# comunicacion_serial.net
KiCad netlist of a schematic drawn in EAGLE
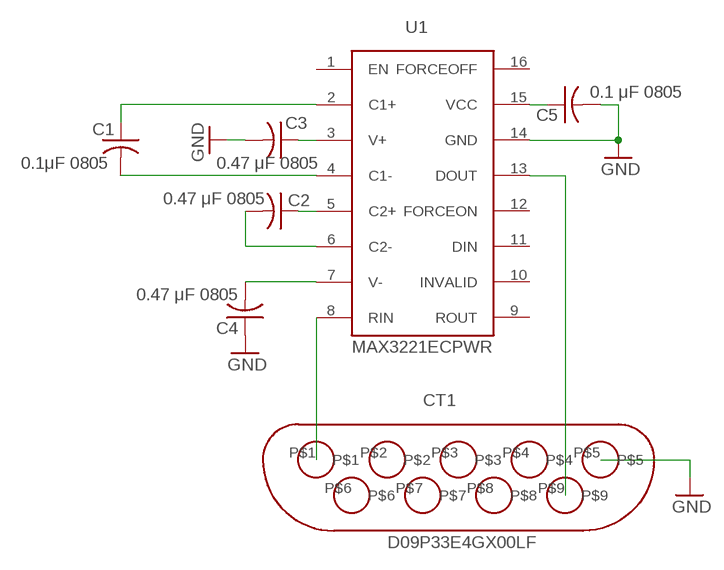
[diagram p0: schematic, sheet 1]

(export (version "E")
  (design (tool "Eeschema 10.0.6"))
  (components
    (comp (ref "C1")
      (value "0.1μF 0805")
      (footprint "eagle-import:C0805")
      (fields (field (name "PARTNO") "GCM21BR72A104KA37L"))
      (libsource (lib "eagle-import") (part "C-USC0805"))
    )
    (comp (ref "C2")
      (value "0.47 μF 0805")
      (footprint "eagle-import:C0805")
      (fields (field (name "PARTNO") "GCM21BR71H474KA55L"))
      (libsource (lib "eagle-import") (part "C-USC0805"))
    )
    (comp (ref "C3")
      (value "0.47 μF 0805")
      (footprint "eagle-import:C0805")
      (fields (field (name "PARTNO") "GCM21BR71H474KA55L"))
      (libsource (lib "eagle-import") (part "C-USC0805"))
    )
    (comp (ref "C4")
      (value "0.47 μF 0805")
      (footprint "eagle-import:C0805")
      (fields (field (name "PARTNO") "GCM21BR71H474KA55L"))
      (libsource (lib "eagle-import") (part "C-USC0805"))
    )
    (comp (ref "C5")
      (value "0.1 μF 0805")
      (footprint "eagle-import:C0805")
      (fields (field (name "PARTNO") "GCM21BR72A104KA37L"))
      (libsource (lib "eagle-import") (part "C-USC0805"))
    )
    (comp (ref "CT1")
      (value "D09P33E4GX00LF")
      (footprint "eagle-import:JEDEC")
      (libsource (lib "eagle-import") (part "D09P33E4GX00LF"))
    )
    (comp (ref "U1")
      (value "MAX3221ECPWR")
      (footprint "eagle-import:TSSOP")
      (libsource (lib "eagle-import") (part "MAX3221ECPWR"))
    )
  )
  (nets
    (net (code "1") (name "GND") (class "Default")
      (node (ref "C3") (pin "2") (pinfunction "2_2") (pintype "passive"))
      (node (ref "C4") (pin "1") (pinfunction "1_1") (pintype "passive"))
      (node (ref "C5") (pin "2") (pinfunction "2_2") (pintype "passive"))
      (node (ref "CT1") (pin "P$5") (pinfunction "P$5_P$5") (pintype "passive"))
      (node (ref "U1") (pin "14") (pinfunction "GND_14") (pintype "power_in"))
    )
    (net (code "2") (name "Net-(U1-C1+)") (class "Default")
      (node (ref "C1") (pin "1") (pinfunction "1_1") (pintype "passive"))
      (node (ref "U1") (pin "2") (pinfunction "C1+_2") (pintype "passive"))
    )
    (net (code "3") (name "Net-(U1-C1-)") (class "Default")
      (node (ref "C1") (pin "2") (pinfunction "2_2") (pintype "passive"))
      (node (ref "U1") (pin "4") (pinfunction "C1-_4") (pintype "passive"))
    )
    (net (code "4") (name "Net-(U1-C2+)") (class "Default")
      (node (ref "C2") (pin "1") (pinfunction "1_1") (pintype "passive"))
      (node (ref "U1") (pin "5") (pinfunction "C2+_5") (pintype "passive"))
    )
    (net (code "5") (name "Net-(U1-C2-)") (class "Default")
      (node (ref "C2") (pin "2") (pinfunction "2_2") (pintype "passive"))
      (node (ref "U1") (pin "6") (pinfunction "C2-_6") (pintype "passive"))
    )
    (net (code "6") (name "Net-(U1-DOUT)") (class "Default")
      (node (ref "CT1") (pin "P$9") (pinfunction "P$9_P$9") (pintype "passive"))
      (node (ref "U1") (pin "13") (pinfunction "DOUT_13") (pintype "output"))
    )
    (net (code "7") (name "Net-(U1-RIN)") (class "Default")
      (node (ref "CT1") (pin "P$1") (pinfunction "P$1_P$1") (pintype "passive"))
      (node (ref "U1") (pin "8") (pinfunction "RIN_8") (pintype "input"))
    )
    (net (code "8") (name "Net-(U1-V+)") (class "Default")
      (node (ref "C3") (pin "1") (pinfunction "1_1") (pintype "passive"))
      (node (ref "U1") (pin "3") (pinfunction "V+_3") (pintype "output"))
    )
    (net (code "9") (name "Net-(U1-V-)") (class "Default")
      (node (ref "C4") (pin "2") (pinfunction "2_2") (pintype "passive"))
      (node (ref "U1") (pin "7") (pinfunction "V-_7") (pintype "output"))
    )
    (net (code "10") (name "Net-(U1-VCC)") (class "Default")
      (node (ref "C5") (pin "1") (pinfunction "1_1") (pintype "passive"))
      (node (ref "U1") (pin "15") (pinfunction "VCC_15") (pintype "power_in"))
    )
    (net (code "11") (name "unconnected-(CT1-PadP$2)") (class "Default")
      (node (ref "CT1") (pin "P$2") (pinfunction "P$2_P$2") (pintype "passive"))
    )
    (net (code "12") (name "unconnected-(CT1-PadP$3)") (class "Default")
      (node (ref "CT1") (pin "P$3") (pinfunction "P$3_P$3") (pintype "passive"))
    )
    (net (code "13") (name "unconnected-(CT1-PadP$4)") (class "Default")
      (node (ref "CT1") (pin "P$4") (pinfunction "P$4_P$4") (pintype "passive"))
    )
    (net (code "14") (name "unconnected-(CT1-PadP$6)") (class "Default")
      (node (ref "CT1") (pin "P$6") (pinfunction "P$6_P$6") (pintype "passive"))
    )
    (net (code "15") (name "unconnected-(CT1-PadP$7)") (class "Default")
      (node (ref "CT1") (pin "P$7") (pinfunction "P$7_P$7") (pintype "passive"))
    )
    (net (code "16") (name "unconnected-(CT1-PadP$8)") (class "Default")
      (node (ref "CT1") (pin "P$8") (pinfunction "P$8_P$8") (pintype "passive"))
    )
    (net (code "17") (name "unconnected-(U1-DIN-Pad11)") (class "Default")
      (node (ref "U1") (pin "11") (pinfunction "DIN_11") (pintype "input"))
    )
    (net (code "18") (name "unconnected-(U1-EN-Pad1)") (class "Default")
      (node (ref "U1") (pin "1") (pinfunction "EN_1") (pintype "input"))
    )
    (net (code "19") (name "unconnected-(U1-FORCEOFF-Pad16)") (class "Default")
      (node (ref "U1") (pin "16") (pinfunction "FORCEOFF_16") (pintype "input"))
    )
    (net (code "20") (name "unconnected-(U1-FORCEON-Pad12)") (class "Default")
      (node (ref "U1") (pin "12") (pinfunction "FORCEON_12") (pintype "input"))
    )
    (net (code "21") (name "unconnected-(U1-INVALID-Pad10)") (class "Default")
      (node (ref "U1") (pin "10") (pinfunction "INVALID_10") (pintype "output"))
    )
    (net (code "22") (name "unconnected-(U1-ROUT-Pad9)") (class "Default")
      (node (ref "U1") (pin "9") (pinfunction "ROUT_9") (pintype "output"))
    )
  )
)
